# baxandall.net
KiCad netlist of a schematic drawn in EAGLE
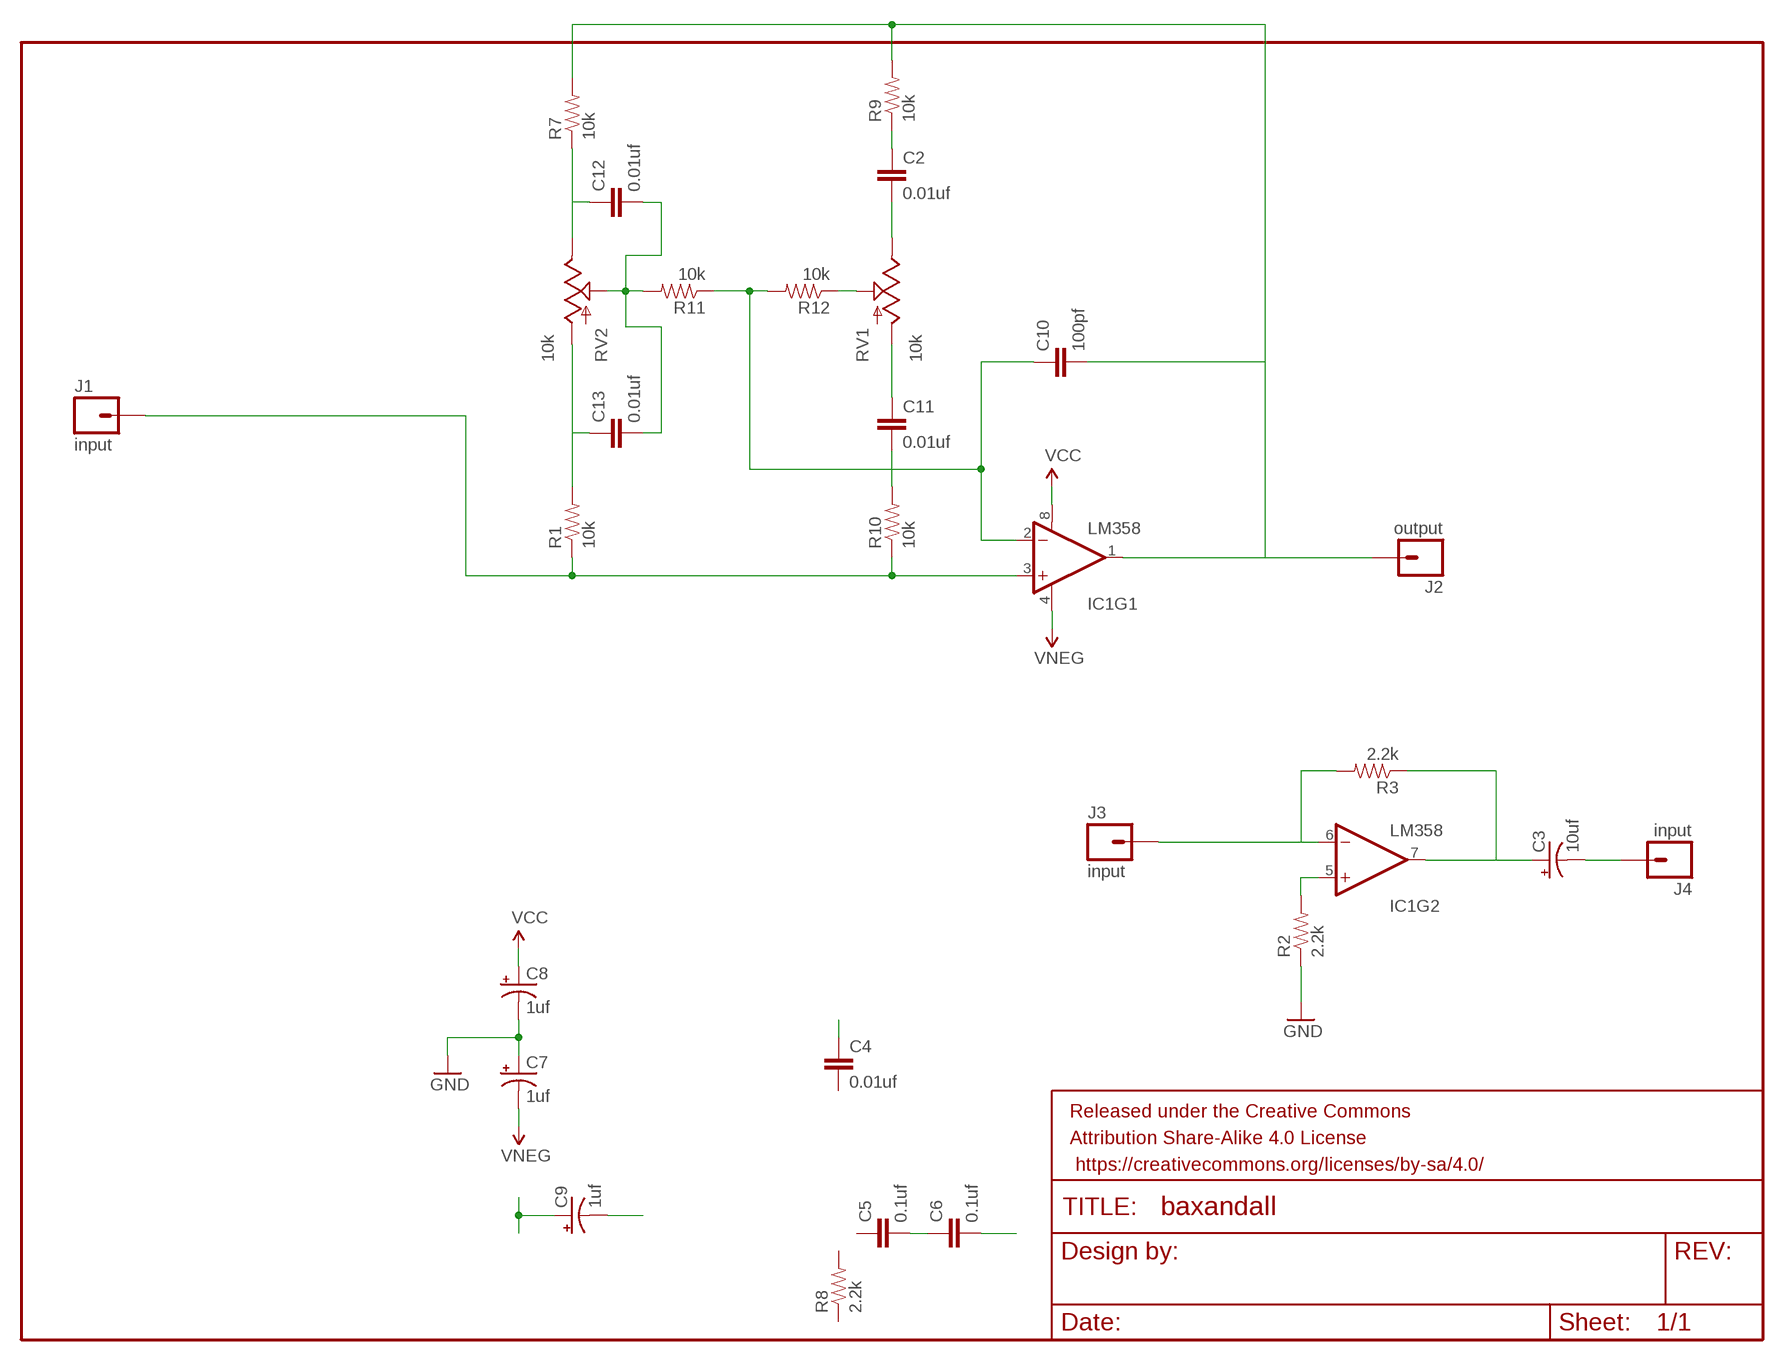
[diagram p0: schematic, sheet 1]

(export (version "E")
  (design (tool "Eeschema 10.0.6"))
  (components
    (comp (ref "C2")
      (value "0.01uf")
      (footprint "eagle-import:CAP-PTH-SMALL")
      (libsource (lib "eagle-import") (part "CAPPTH"))
    )
    (comp (ref "C3")
      (value "10uf")
      (footprint "eagle-import:CPOL-RADIAL-10UF-25V")
      (libsource (lib "eagle-import") (part "10UF-25V-20%(PTH)"))
    )
    (comp (ref "C4")
      (value "0.01uf")
      (footprint "eagle-import:CAP-PTH-SMALL")
      (libsource (lib "eagle-import") (part "CAPPTH"))
    )
    (comp (ref "C5")
      (value "0.1uf")
      (footprint "eagle-import:CAP-PTH-SMALL")
      (libsource (lib "eagle-import") (part "CAPPTH"))
    )
    (comp (ref "C6")
      (value "0.1uf")
      (footprint "eagle-import:CAP-PTH-SMALL")
      (libsource (lib "eagle-import") (part "CAPPTH"))
    )
    (comp (ref "C7")
      (value "1uf")
      (footprint "eagle-import:CPOL-RADIAL-10UF-25V")
      (libsource (lib "eagle-import") (part "CAP_POLPTH2"))
    )
    (comp (ref "C8")
      (value "1uf")
      (footprint "eagle-import:CPOL-RADIAL-10UF-25V")
      (libsource (lib "eagle-import") (part "CAP_POLPTH2"))
    )
    (comp (ref "C9")
      (value "1uf")
      (footprint "eagle-import:CPOL-RADIAL-10UF-25V")
      (libsource (lib "eagle-import") (part "CAP_POLPTH2"))
    )
    (comp (ref "C10")
      (value "100pf")
      (footprint "eagle-import:CAP-PTH-SMALL")
      (libsource (lib "eagle-import") (part "CAPPTH"))
    )
    (comp (ref "C11")
      (value "0.01uf")
      (footprint "eagle-import:CAP-PTH-SMALL")
      (libsource (lib "eagle-import") (part "CAPPTH"))
    )
    (comp (ref "C12")
      (value "0.01uf")
      (footprint "eagle-import:CAP-PTH-SMALL")
      (libsource (lib "eagle-import") (part "CAPPTH"))
    )
    (comp (ref "C13")
      (value "0.01uf")
      (footprint "eagle-import:CAP-PTH-SMALL")
      (libsource (lib "eagle-import") (part "CAPPTH"))
    )
    (comp (ref "FRAME1")
      (value "FRAME-LETTER")
      (footprint "eagle-import:CREATIVE_COMMONS")
      (libsource (lib "eagle-import") (part "FRAME-LETTER"))
    )
    (comp (ref "IC1")
      (value "LM358")
      (footprint "eagle-import:DIP08")
      (libsource (lib "eagle-import") (part "LM358"))
    )
    (comp (ref "J1")
      (value "input")
      (footprint "eagle-import:1X01NS-KIT")
      (libsource (lib "eagle-import") (part "M01NOSILK-KIT"))
    )
    (comp (ref "J2")
      (value "output")
      (footprint "eagle-import:1X01NS-KIT")
      (libsource (lib "eagle-import") (part "M01NOSILK-KIT"))
    )
    (comp (ref "J3")
      (value "input")
      (footprint "eagle-import:1X01NS-KIT")
      (libsource (lib "eagle-import") (part "M01NOSILK-KIT"))
    )
    (comp (ref "J4")
      (value "input")
      (footprint "eagle-import:1X01NS-KIT")
      (libsource (lib "eagle-import") (part "M01NOSILK-KIT"))
    )
    (comp (ref "R1")
      (value "10k")
      (footprint "eagle-import:AXIAL-0.3")
      (libsource (lib "eagle-import") (part "10KOHM-1/4W-1%(PTH)HORIZ"))
    )
    (comp (ref "R2")
      (value "2.2k")
      (footprint "eagle-import:AXIAL-0.3")
      (libsource (lib "eagle-import") (part "RESISTORAXIAL-0.3"))
    )
    (comp (ref "R3")
      (value "2.2k")
      (footprint "eagle-import:AXIAL-0.3")
      (libsource (lib "eagle-import") (part "RESISTORAXIAL-0.3"))
    )
    (comp (ref "R7")
      (value "10k")
      (footprint "eagle-import:AXIAL-0.3")
      (libsource (lib "eagle-import") (part "10KOHM-1/4W-1%(PTH)HORIZ"))
    )
    (comp (ref "R8")
      (value "2.2k")
      (footprint "eagle-import:AXIAL-0.3")
      (libsource (lib "eagle-import") (part "RESISTORAXIAL-0.3"))
    )
    (comp (ref "R9")
      (value "10k")
      (footprint "eagle-import:AXIAL-0.3")
      (libsource (lib "eagle-import") (part "10KOHM-1/4W-1%(PTH)HORIZ"))
    )
    (comp (ref "R10")
      (value "10k")
      (footprint "eagle-import:AXIAL-0.3")
      (libsource (lib "eagle-import") (part "10KOHM-1/4W-1%(PTH)HORIZ"))
    )
    (comp (ref "R11")
      (value "10k")
      (footprint "eagle-import:AXIAL-0.3")
      (libsource (lib "eagle-import") (part "10KOHM-1/4W-1%(PTH)HORIZ"))
    )
    (comp (ref "R12")
      (value "10k")
      (footprint "eagle-import:AXIAL-0.3")
      (libsource (lib "eagle-import") (part "10KOHM-1/4W-1%(PTH)HORIZ"))
    )
    (comp (ref "RV1")
      (value "10k")
      (footprint "eagle-import:POT_ALPHA_RV16AF-20")
      (libsource (lib "eagle-import") (part "POT-RV16AF-20"))
    )
    (comp (ref "RV2")
      (value "10k")
      (footprint "eagle-import:POT_ALPHA_RV16AF-20")
      (libsource (lib "eagle-import") (part "POT-RV16AF-20"))
    )
  )
  (nets
    (net (code "1") (name "GND") (class "Default")
      (node (ref "C7") (pin "1") (pinfunction "+_1") (pintype "passive"))
      (node (ref "C8") (pin "2") (pinfunction "-_2") (pintype "passive"))
      (node (ref "R2") (pin "P$1") (pinfunction "1_P$1") (pintype "passive"))
    )
    (net (code "2") (name "Net-(C3-+)") (class "Default")
      (node (ref "C3") (pin "1") (pinfunction "+_1") (pintype "passive"))
      (node (ref "IC1") (pin "7") (pinfunction "OUT_7") (pintype "output"))
      (node (ref "R3") (pin "P$1") (pinfunction "1_P$1") (pintype "passive"))
    )
    (net (code "3") (name "Net-(C3--)") (class "Default")
      (node (ref "C3") (pin "2") (pinfunction "-_2") (pintype "passive"))
      (node (ref "J4") (pin "1") (pinfunction "1_1") (pintype "passive"))
    )
    (net (code "4") (name "Net-(C5-Pad2)") (class "Default")
      (node (ref "C5") (pin "2") (pinfunction "2_2") (pintype "passive"))
      (node (ref "C6") (pin "1") (pinfunction "1_1") (pintype "passive"))
    )
    (net (code "5") (name "Net-(IC1A-+IN)") (class "Default")
      (node (ref "IC1") (pin "3") (pinfunction "+IN_3") (pintype "input"))
      (node (ref "J1") (pin "1") (pinfunction "1_1") (pintype "passive"))
      (node (ref "R1") (pin "P$1") (pinfunction "1_P$1") (pintype "passive"))
      (node (ref "R10") (pin "P$1") (pinfunction "1_P$1") (pintype "passive"))
    )
    (net (code "6") (name "Net-(IC1A--IN)") (class "Default")
      (node (ref "C10") (pin "1") (pinfunction "1_1") (pintype "passive"))
      (node (ref "IC1") (pin "2") (pinfunction "-IN_2") (pintype "input"))
      (node (ref "R11") (pin "P$1") (pinfunction "1_P$1") (pintype "passive"))
      (node (ref "R12") (pin "P$2") (pinfunction "2_P$2") (pintype "passive"))
    )
    (net (code "7") (name "Net-(IC1A-OUT)") (class "Default")
      (node (ref "C10") (pin "2") (pinfunction "2_2") (pintype "passive"))
      (node (ref "IC1") (pin "1") (pinfunction "OUT_1") (pintype "output"))
      (node (ref "J2") (pin "1") (pinfunction "1_1") (pintype "passive"))
      (node (ref "R7") (pin "P$2") (pinfunction "2_P$2") (pintype "passive"))
      (node (ref "R9") (pin "P$2") (pinfunction "2_P$2") (pintype "passive"))
    )
    (net (code "8") (name "Net-(IC1B-+IN)") (class "Default")
      (node (ref "IC1") (pin "5") (pinfunction "+IN_5") (pintype "input"))
      (node (ref "R2") (pin "P$2") (pinfunction "2_P$2") (pintype "passive"))
    )
    (net (code "9") (name "Net-(IC1B--IN)") (class "Default")
      (node (ref "IC1") (pin "6") (pinfunction "-IN_6") (pintype "input"))
      (node (ref "J3") (pin "1") (pinfunction "1_1") (pintype "passive"))
      (node (ref "R3") (pin "P$2") (pinfunction "2_P$2") (pintype "passive"))
    )
    (net (code "10") (name "Net-(R1-2)") (class "Default")
      (node (ref "C13") (pin "1") (pinfunction "1_1") (pintype "passive"))
      (node (ref "R1") (pin "P$2") (pinfunction "2_P$2") (pintype "passive"))
      (node (ref "RV2") (pin "1") (pinfunction "A_1") (pintype "passive"))
    )
    (net (code "11") (name "Net-(R7-1)") (class "Default")
      (node (ref "C12") (pin "1") (pinfunction "1_1") (pintype "passive"))
      (node (ref "R7") (pin "P$1") (pinfunction "1_P$1") (pintype "passive"))
      (node (ref "RV2") (pin "3") (pinfunction "E_3") (pintype "passive"))
    )
    (net (code "12") (name "Net-(R9-1)") (class "Default")
      (node (ref "C2") (pin "1") (pinfunction "1_1") (pintype "passive"))
      (node (ref "R9") (pin "P$1") (pinfunction "1_P$1") (pintype "passive"))
    )
    (net (code "13") (name "Net-(R10-2)") (class "Default")
      (node (ref "C11") (pin "2") (pinfunction "2_2") (pintype "passive"))
      (node (ref "R10") (pin "P$2") (pinfunction "2_P$2") (pintype "passive"))
    )
    (net (code "14") (name "Net-(R11-2)") (class "Default")
      (node (ref "C12") (pin "2") (pinfunction "2_2") (pintype "passive"))
      (node (ref "C13") (pin "2") (pinfunction "2_2") (pintype "passive"))
      (node (ref "R11") (pin "P$2") (pinfunction "2_P$2") (pintype "passive"))
      (node (ref "RV2") (pin "2") (pinfunction "S_2") (pintype "passive"))
    )
    (net (code "15") (name "Net-(R12-1)") (class "Default")
      (node (ref "R12") (pin "P$1") (pinfunction "1_P$1") (pintype "passive"))
      (node (ref "RV1") (pin "2") (pinfunction "S_2") (pintype "passive"))
    )
    (net (code "16") (name "Net-(RV1-A)") (class "Default")
      (node (ref "C11") (pin "1") (pinfunction "1_1") (pintype "passive"))
      (node (ref "RV1") (pin "1") (pinfunction "A_1") (pintype "passive"))
    )
    (net (code "17") (name "Net-(RV1-E)") (class "Default")
      (node (ref "C2") (pin "2") (pinfunction "2_2") (pintype "passive"))
      (node (ref "RV1") (pin "3") (pinfunction "E_3") (pintype "passive"))
    )
    (net (code "18") (name "VCC") (class "Default")
      (node (ref "C8") (pin "1") (pinfunction "+_1") (pintype "passive"))
      (node (ref "IC1") (pin "8") (pinfunction "V+_8") (pintype "power_in"))
    )
    (net (code "19") (name "VNEG") (class "Default")
      (node (ref "C7") (pin "2") (pinfunction "-_2") (pintype "passive"))
      (node (ref "IC1") (pin "4") (pinfunction "V-_4") (pintype "power_in"))
    )
    (net (code "20") (name "unconnected-(C4-Pad1)") (class "Default")
      (node (ref "C4") (pin "1") (pinfunction "1_1") (pintype "passive"))
    )
    (net (code "21") (name "unconnected-(C4-Pad2)") (class "Default")
      (node (ref "C4") (pin "2") (pinfunction "2_2") (pintype "passive"))
    )
    (net (code "22") (name "unconnected-(C5-Pad1)") (class "Default")
      (node (ref "C5") (pin "1") (pinfunction "1_1") (pintype "passive"))
    )
    (net (code "23") (name "unconnected-(C6-Pad2)") (class "Default")
      (node (ref "C6") (pin "2") (pinfunction "2_2") (pintype "passive"))
    )
    (net (code "24") (name "unconnected-(C9-+-Pad1)") (class "Default")
      (node (ref "C9") (pin "1") (pinfunction "+_1") (pintype "passive"))
    )
    (net (code "25") (name "unconnected-(C9---Pad2)") (class "Default")
      (node (ref "C9") (pin "2") (pinfunction "-_2") (pintype "passive"))
    )
    (net (code "26") (name "unconnected-(R8-1-PadP$1)") (class "Default")
      (node (ref "R8") (pin "P$1") (pinfunction "1_P$1") (pintype "passive"))
    )
    (net (code "27") (name "unconnected-(R8-2-PadP$2)") (class "Default")
      (node (ref "R8") (pin "P$2") (pinfunction "2_P$2") (pintype "passive"))
    )
  )
)
